# SLAMP.net
KiCad netlist of a schematic drawn in EAGLE
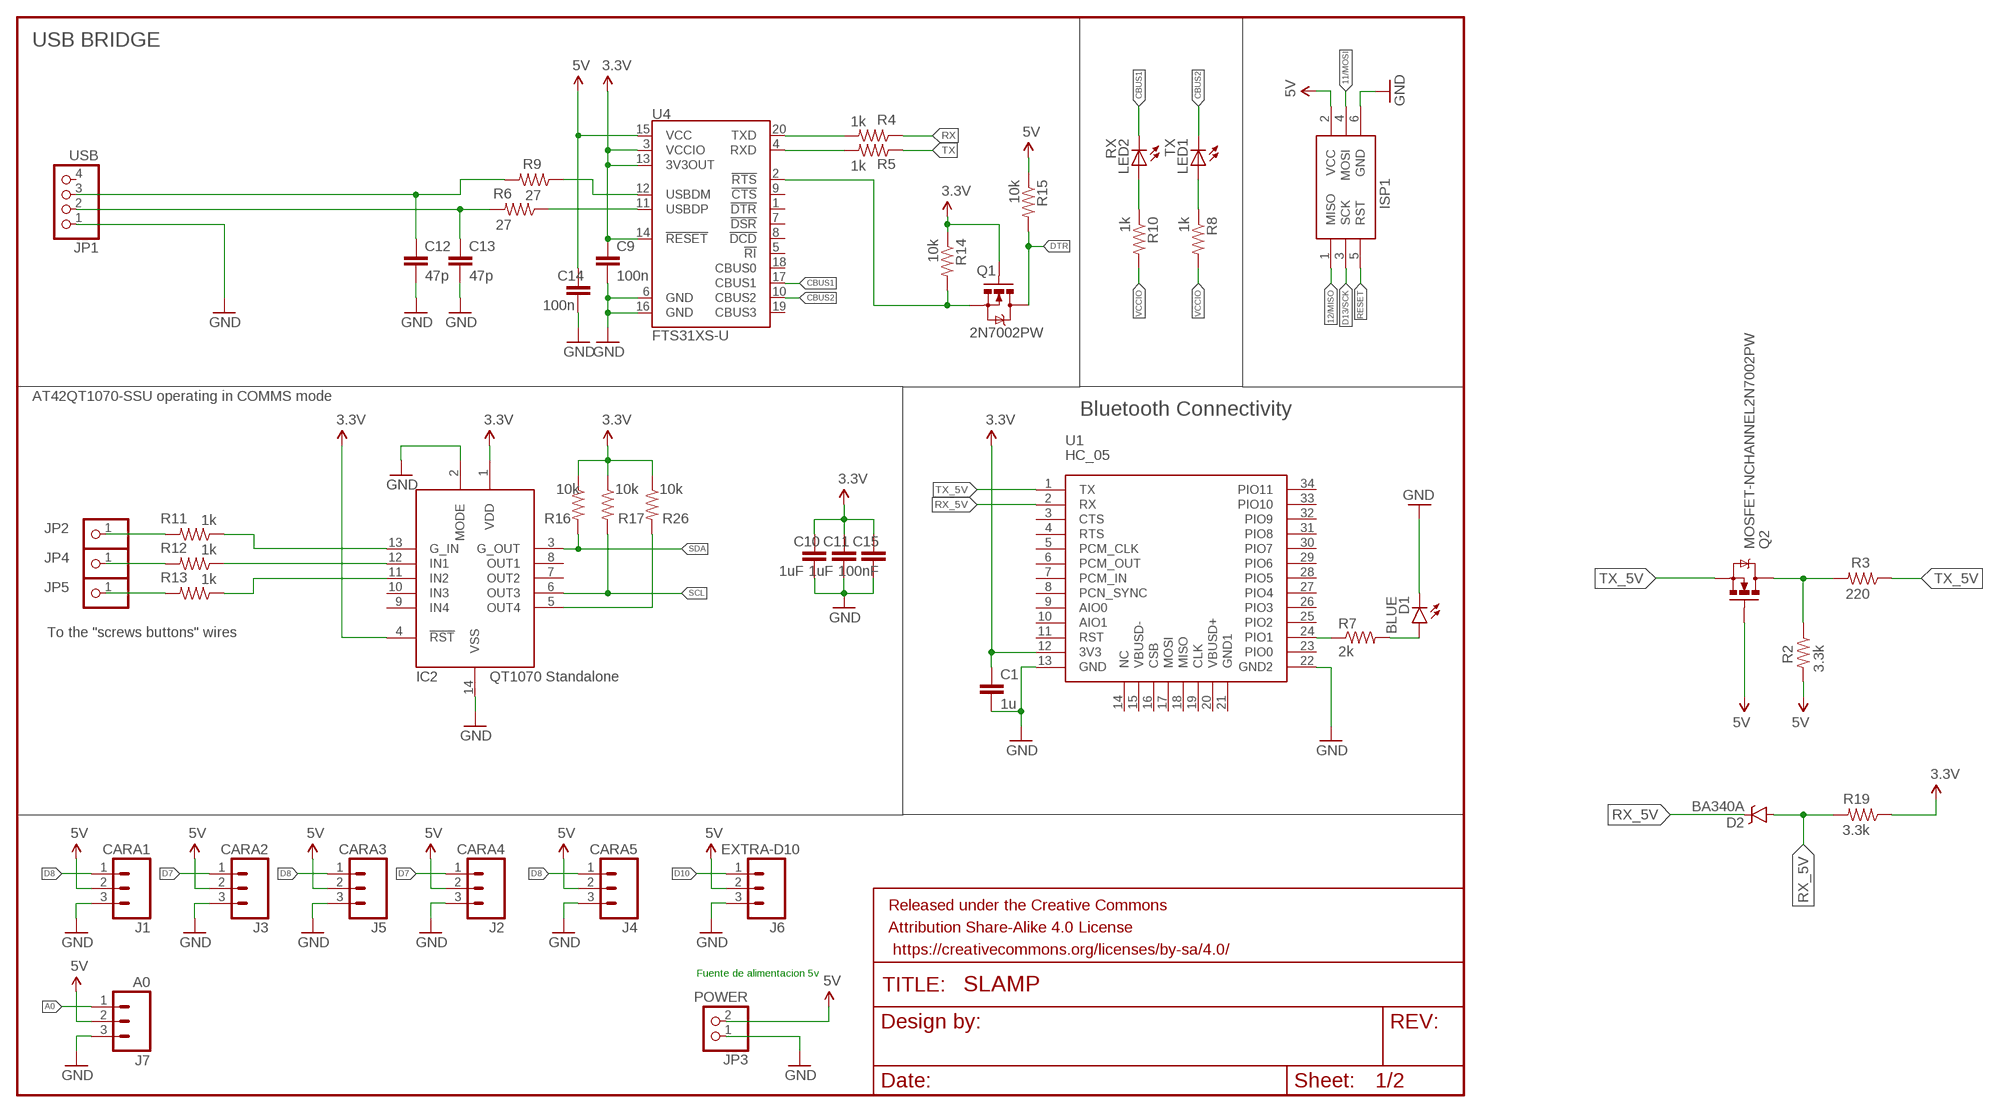
[diagram p0: schematic, sheet 1]
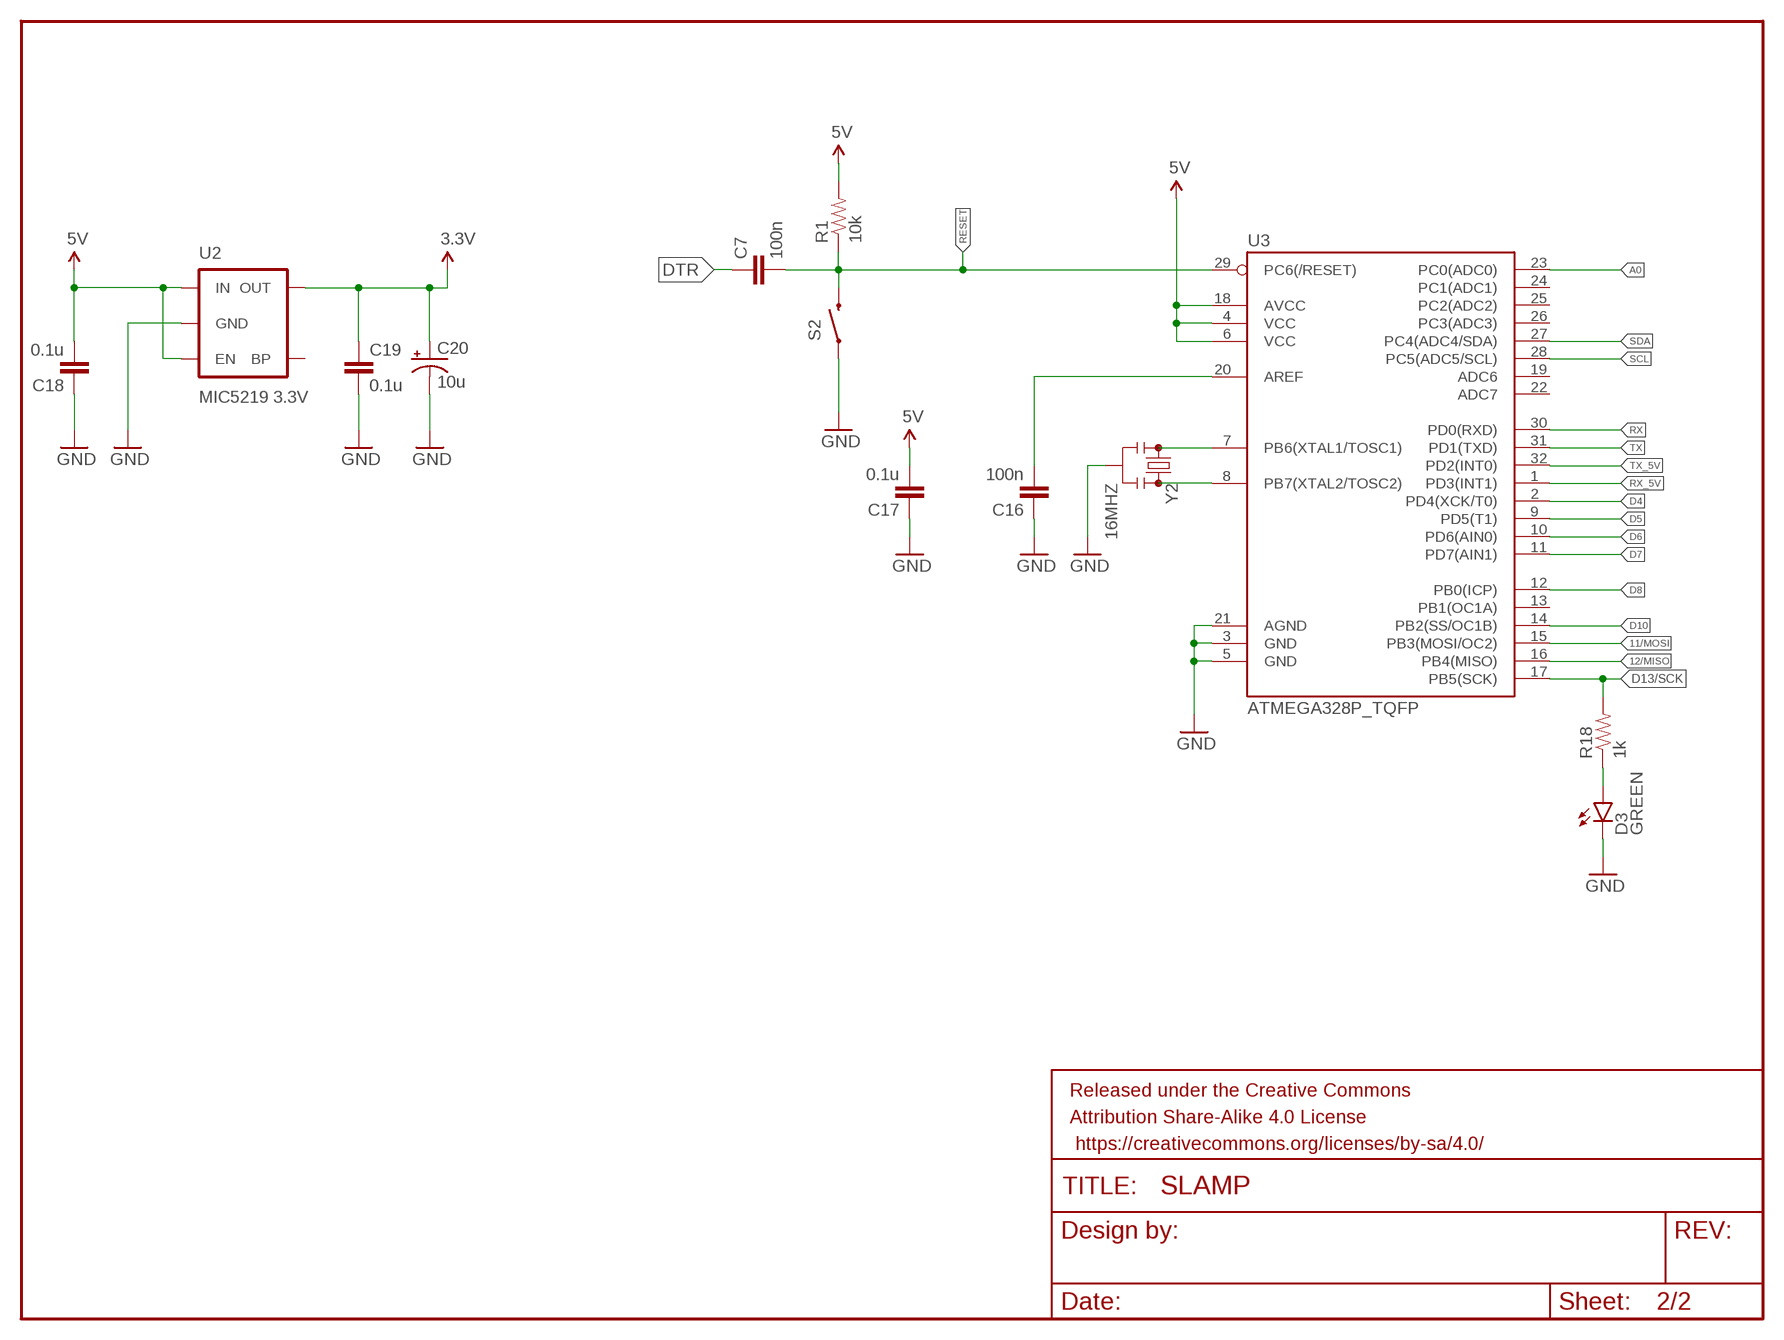
[diagram p1: schematic, sheet 2]

(export (version "E")
  (design (tool "Eeschema 10.0.6"))
  (components
    (comp (ref "C1")
      (value "1u")
      (footprint "eagle-import:0603-CAP")
      (libsource (lib "eagle-import") (part "CAP0603-CAP"))
    )
    (comp (ref "C9")
      (value "100n")
      (footprint "eagle-import:0603-CAP")
      (libsource (lib "eagle-import") (part "CAP0603-CAP"))
    )
    (comp (ref "C10")
      (value "1uF")
      (footprint "eagle-import:0603-CAP")
      (libsource (lib "eagle-import") (part "CAP0603-CAP"))
    )
    (comp (ref "C11")
      (value "1uF")
      (footprint "eagle-import:0603-CAP")
      (libsource (lib "eagle-import") (part "CAP0603-CAP"))
    )
    (comp (ref "C12")
      (value "47p")
      (footprint "eagle-import:0603-CAP")
      (libsource (lib "eagle-import") (part "CAP0603-CAP"))
    )
    (comp (ref "C13")
      (value "47p")
      (footprint "eagle-import:0603-CAP")
      (libsource (lib "eagle-import") (part "CAP0603-CAP"))
    )
    (comp (ref "C14")
      (value "100n")
      (footprint "eagle-import:0603-CAP")
      (libsource (lib "eagle-import") (part "CAP0603-CAP"))
    )
    (comp (ref "C15")
      (value "100nF")
      (footprint "eagle-import:0603-CAP")
      (libsource (lib "eagle-import") (part "CAP0603-CAP"))
    )
    (comp (ref "D1")
      (value "BLUE")
      (footprint "eagle-import:LED-0603")
      (libsource (lib "eagle-import") (part "LED-BLUE0603"))
    )
    (comp (ref "D2")
      (value "BA340A")
      (footprint "eagle-import:SMA-DIODE")
      (libsource (lib "eagle-import") (part "B340A"))
    )
    (comp (ref "FRAME1")
      (value "FRAME-LETTERNO_PACKAGE")
      (footprint "eagle-import:DUMMY")
      (fields (field (name "DESIGNER") "Nobody"))
      (libsource (lib "eagle-import") (part "FRAME-LETTERNO_PACKAGE"))
    )
    (comp (ref "IC2")
      (value "AT42QT1070-SSU")
      (footprint "eagle-import:SO14")
      (libsource (lib "eagle-import") (part "AT42QT1070-SSU"))
    )
    (comp (ref "ISP1")
      (value "AVRISP-6")
      (footprint "eagle-import:AVRISP")
      (libsource (lib "eagle-import") (part "AVRISP-6"))
    )
    (comp (ref "J1")
      (value "CARA1")
      (footprint "eagle-import:JST-3-PTH-VERT")
      (libsource (lib "eagle-import") (part "M03JST-PTH-VERT"))
    )
    (comp (ref "J2")
      (value "CARA4")
      (footprint "eagle-import:JST-3-PTH-VERT")
      (libsource (lib "eagle-import") (part "M03JST-PTH-VERT"))
    )
    (comp (ref "J3")
      (value "CARA2")
      (footprint "eagle-import:JST-3-PTH-VERT")
      (libsource (lib "eagle-import") (part "M03JST-PTH-VERT"))
    )
    (comp (ref "J4")
      (value "CARA5")
      (footprint "eagle-import:JST-3-PTH-VERT")
      (libsource (lib "eagle-import") (part "M03JST-PTH-VERT"))
    )
    (comp (ref "J5")
      (value "CARA3")
      (footprint "eagle-import:JST-3-PTH-VERT")
      (libsource (lib "eagle-import") (part "M03JST-PTH-VERT"))
    )
    (comp (ref "J6")
      (value "EXTRA-D10")
      (footprint "eagle-import:JST-3-PTH-VERT")
      (libsource (lib "eagle-import") (part "M03JST-PTH-VERT"))
    )
    (comp (ref "J7")
      (value "A0")
      (footprint "eagle-import:JST-3-PTH-VERT")
      (libsource (lib "eagle-import") (part "M03JST-PTH-VERT"))
    )
    (comp (ref "JP1")
      (value "USB")
      (footprint "eagle-import:1X04")
      (libsource (lib "eagle-import") (part "PINHD-1X4"))
    )
    (comp (ref "JP2")
      (value "PINHD-1X1")
      (footprint "eagle-import:1X01")
      (libsource (lib "eagle-import") (part "PINHD-1X1"))
    )
    (comp (ref "JP3")
      (value "POWER")
      (footprint "eagle-import:1X02")
      (libsource (lib "eagle-import") (part "PINHD-1X2"))
    )
    (comp (ref "JP4")
      (value "PINHD-1X1")
      (footprint "eagle-import:1X01")
      (libsource (lib "eagle-import") (part "PINHD-1X1"))
    )
    (comp (ref "JP5")
      (value "PINHD-1X1")
      (footprint "eagle-import:1X01")
      (libsource (lib "eagle-import") (part "PINHD-1X1"))
    )
    (comp (ref "LED1")
      (value "TX")
      (footprint "eagle-import:CHIP-LED0603")
      (libsource (lib "eagle-import") (part "LEDCHIP-LED0603"))
    )
    (comp (ref "LED2")
      (value "RX")
      (footprint "eagle-import:CHIP-LED0603")
      (libsource (lib "eagle-import") (part "LEDCHIP-LED0603"))
    )
    (comp (ref "Q1")
      (value "2N7002PW")
      (footprint "eagle-import:SOT323")
      (libsource (lib "eagle-import") (part "MOSFET-NCHANNEL2N7002PW"))
    )
    (comp (ref "Q2")
      (value "MOSFET-NCHANNEL2N7002PW")
      (footprint "eagle-import:SOT323")
      (libsource (lib "eagle-import") (part "MOSFET-NCHANNEL2N7002PW"))
    )
    (comp (ref "R2")
      (value "3.3k")
      (footprint "eagle-import:0603-RES")
      (libsource (lib "eagle-import") (part "RESISTOR0603-RES"))
    )
    (comp (ref "R3")
      (value "220")
      (footprint "eagle-import:0603-RES")
      (libsource (lib "eagle-import") (part "RESISTOR0603-RES"))
    )
    (comp (ref "R4")
      (value "1k")
      (footprint "eagle-import:0805")
      (libsource (lib "eagle-import") (part "RESISTOR0805-RES"))
    )
    (comp (ref "R5")
      (value "1k")
      (footprint "eagle-import:0805")
      (libsource (lib "eagle-import") (part "RESISTOR0805-RES"))
    )
    (comp (ref "R6")
      (value "27")
      (footprint "eagle-import:0603-RES")
      (libsource (lib "eagle-import") (part "RESISTOR0603-RES"))
    )
    (comp (ref "R7")
      (value "2k")
      (footprint "eagle-import:0805")
      (libsource (lib "eagle-import") (part "RESISTOR0805-RES"))
    )
    (comp (ref "R8")
      (value "1k")
      (footprint "eagle-import:0603-RES")
      (libsource (lib "eagle-import") (part "RESISTOR0603-RES"))
    )
    (comp (ref "R9")
      (value "27")
      (footprint "eagle-import:0603-RES")
      (libsource (lib "eagle-import") (part "RESISTOR0603-RES"))
    )
    (comp (ref "R10")
      (value "1k")
      (footprint "eagle-import:0603-RES")
      (libsource (lib "eagle-import") (part "RESISTOR0603-RES"))
    )
    (comp (ref "R11")
      (value "1k")
      (footprint "eagle-import:0603-RES")
      (libsource (lib "eagle-import") (part "RESISTOR0603-RES"))
    )
    (comp (ref "R12")
      (value "1k")
      (footprint "eagle-import:0603-RES")
      (libsource (lib "eagle-import") (part "RESISTOR0603-RES"))
    )
    (comp (ref "R13")
      (value "1k")
      (footprint "eagle-import:0603-RES")
      (libsource (lib "eagle-import") (part "RESISTOR0603-RES"))
    )
    (comp (ref "R14")
      (value "10k")
      (footprint "eagle-import:0805")
      (libsource (lib "eagle-import") (part "RESISTOR0805-RES"))
    )
    (comp (ref "R15")
      (value "10k")
      (footprint "eagle-import:0805")
      (libsource (lib "eagle-import") (part "RESISTOR0805-RES"))
    )
    (comp (ref "R16")
      (value "10k")
      (footprint "eagle-import:0603-RES")
      (libsource (lib "eagle-import") (part "RESISTOR0603-RES"))
    )
    (comp (ref "R17")
      (value "10k")
      (footprint "eagle-import:0603-RES")
      (libsource (lib "eagle-import") (part "RESISTOR0603-RES"))
    )
    (comp (ref "R19")
      (value "3.3k")
      (footprint "eagle-import:0603-RES")
      (libsource (lib "eagle-import") (part "RESISTOR0603-RES"))
    )
    (comp (ref "R26")
      (value "10k")
      (footprint "eagle-import:0603-RES")
      (libsource (lib "eagle-import") (part "RESISTOR0603-RES"))
    )
    (comp (ref "U1")
      (value "HC_05")
      (footprint "eagle-import:BLUETOOTH_SMD")
      (libsource (lib "eagle-import") (part "HC_05"))
    )
    (comp (ref "U4")
      (value "FTS31XS-U")
      (footprint "eagle-import:SSOP20_L")
      (libsource (lib "eagle-import") (part "FT231XS"))
    )
    (comp (ref "C7")
      (value "100n")
      (footprint "eagle-import:0805")
      (libsource (lib "eagle-import") (part "CAP0805"))
    )
    (comp (ref "C16")
      (value "100n")
      (footprint "eagle-import:0805")
      (libsource (lib "eagle-import") (part "CAP0805"))
    )
    (comp (ref "C17")
      (value "0.1u")
      (footprint "eagle-import:0805")
      (libsource (lib "eagle-import") (part "CAP0805"))
    )
    (comp (ref "C18")
      (value "0.1u")
      (footprint "eagle-import:0603-CAP")
      (libsource (lib "eagle-import") (part "CAP0603-CAP"))
    )
    (comp (ref "C19")
      (value "0.1u")
      (footprint "eagle-import:0603-CAP")
      (libsource (lib "eagle-import") (part "CAP0603-CAP"))
    )
    (comp (ref "C20")
      (value "10u")
      (footprint "eagle-import:SMC_P")
      (libsource (lib "eagle-import") (part "CPOL-USSMCP"))
    )
    (comp (ref "D3")
      (value "GREEN")
      (footprint "eagle-import:LED-0603")
      (libsource (lib "eagle-import") (part "LED-BLUE0603"))
    )
    (comp (ref "FRAME2")
      (value "FRAME-LETTERNO_PACKAGE")
      (footprint "eagle-import:DUMMY")
      (fields (field (name "DESIGNER") "Nobody"))
      (libsource (lib "eagle-import") (part "FRAME-LETTERNO_PACKAGE"))
    )
    (comp (ref "R1")
      (value "10k")
      (footprint "eagle-import:0805")
      (libsource (lib "eagle-import") (part "RESISTOR0805-RES"))
    )
    (comp (ref "R18")
      (value "1k")
      (footprint "eagle-import:0805")
      (libsource (lib "eagle-import") (part "RESISTOR0805-RES"))
    )
    (comp (ref "S2")
      (value "SWITCH-MOMENTARY-2PTH")
      (footprint "eagle-import:TACTILE-PTH")
      (libsource (lib "eagle-import") (part "SWITCH-MOMENTARY-2PTH"))
    )
    (comp (ref "U2")
      (value "MIC5219 3.3V")
      (footprint "eagle-import:SOT23-5")
      (libsource (lib "eagle-import") (part "V_REG_MIC52193.3V"))
    )
    (comp (ref "U3")
      (value "ATMEGA328P_TQFP")
      (footprint "eagle-import:TQFP32-08")
      (libsource (lib "eagle-import") (part "ATMEGA328P_TQFP"))
    )
    (comp (ref "Y2")
      (value "16MHZ")
      (footprint "eagle-import:RESONATOR-SMD")
      (libsource (lib "eagle-import") (part "RESONATOR16MHZ"))
    )
  )
  (nets
    (net (code "1") (name "3.3V") (class "Default")
      (node (ref "C1") (pin "1") (pinfunction "1_1") (pintype "passive"))
      (node (ref "C10") (pin "1") (pinfunction "1_1") (pintype "passive"))
      (node (ref "C11") (pin "1") (pinfunction "1_1") (pintype "passive"))
      (node (ref "C15") (pin "1") (pinfunction "1_1") (pintype "passive"))
      (node (ref "C19") (pin "1") (pinfunction "1_1") (pintype "passive"))
      (node (ref "C20") (pin "+") (pinfunction "+_+") (pintype "passive"))
      (node (ref "C9") (pin "1") (pinfunction "1_1") (pintype "passive"))
      (node (ref "IC2") (pin "1") (pinfunction "VDD_1") (pintype "power_in"))
      (node (ref "IC2") (pin "4") (pinfunction "~{RST}_4") (pintype "input"))
      (node (ref "Q1") (pin "1") (pinfunction "G_1") (pintype "passive"))
      (node (ref "R14") (pin "1") (pinfunction "1_1") (pintype "passive"))
      (node (ref "R16") (pin "1") (pinfunction "1_1") (pintype "passive"))
      (node (ref "R17") (pin "1") (pinfunction "1_1") (pintype "passive"))
      (node (ref "R19") (pin "1") (pinfunction "1_1") (pintype "passive"))
      (node (ref "R26") (pin "1") (pinfunction "1_1") (pintype "passive"))
      (node (ref "U1") (pin "12") (pinfunction "3V3_12") (pintype "bidirectional"))
      (node (ref "U2") (pin "5") (pinfunction "OUT_5") (pintype "passive"))
      (node (ref "U4") (pin "13") (pinfunction "3V3OUT_13") (pintype "bidirectional"))
      (node (ref "U4") (pin "14") (pinfunction "~{RESET}_14") (pintype "bidirectional"))
      (node (ref "U4") (pin "3") (pinfunction "VCCIO_3") (pintype "bidirectional"))
    )
    (net (code "2") (name "5V") (class "Default")
      (node (ref "C14") (pin "1") (pinfunction "1_1") (pintype "passive"))
      (node (ref "C17") (pin "2") (pinfunction "2_2") (pintype "passive"))
      (node (ref "C18") (pin "2") (pinfunction "2_2") (pintype "passive"))
      (node (ref "ISP1") (pin "2") (pinfunction "VCC_2") (pintype "power_in"))
      (node (ref "J1") (pin "2") (pinfunction "2_2") (pintype "passive"))
      (node (ref "J2") (pin "2") (pinfunction "2_2") (pintype "passive"))
      (node (ref "J3") (pin "2") (pinfunction "2_2") (pintype "passive"))
      (node (ref "J4") (pin "2") (pinfunction "2_2") (pintype "passive"))
      (node (ref "J5") (pin "2") (pinfunction "2_2") (pintype "passive"))
      (node (ref "J6") (pin "2") (pinfunction "2_2") (pintype "passive"))
      (node (ref "J7") (pin "2") (pinfunction "2_2") (pintype "passive"))
      (node (ref "JP3") (pin "2") (pinfunction "2_2") (pintype "passive"))
      (node (ref "Q2") (pin "1") (pinfunction "G_1") (pintype "passive"))
      (node (ref "R1") (pin "2") (pinfunction "2_2") (pintype "passive"))
      (node (ref "R15") (pin "1") (pinfunction "1_1") (pintype "passive"))
      (node (ref "R2") (pin "2") (pinfunction "2_2") (pintype "passive"))
      (node (ref "U2") (pin "1") (pinfunction "IN_1") (pintype "input"))
      (node (ref "U2") (pin "3") (pinfunction "EN_3") (pintype "input"))
      (node (ref "U3") (pin "18") (pinfunction "AVCC_18") (pintype "bidirectional"))
      (node (ref "U3") (pin "4") (pinfunction "VCC_4") (pintype "bidirectional"))
      (node (ref "U3") (pin "6") (pinfunction "VCC_6") (pintype "bidirectional"))
      (node (ref "U4") (pin "15") (pinfunction "VCC_15") (pintype "bidirectional"))
    )
    (net (code "3") (name "11{slash}MOSI") (class "Default")
      (node (ref "ISP1") (pin "4") (pinfunction "MOSI_4") (pintype "output"))
      (node (ref "U3") (pin "15") (pinfunction "PB3(MOSI/OC2)_15") (pintype "bidirectional"))
    )
    (net (code "4") (name "12{slash}MISO") (class "Default")
      (node (ref "ISP1") (pin "1") (pinfunction "MISO_1") (pintype "input"))
      (node (ref "U3") (pin "16") (pinfunction "PB4(MISO)_16") (pintype "bidirectional"))
    )
    (net (code "5") (name "A0") (class "Default")
      (node (ref "J7") (pin "1") (pinfunction "1_1") (pintype "passive"))
      (node (ref "U3") (pin "23") (pinfunction "PC0(ADC0)_23") (pintype "bidirectional"))
    )
    (net (code "6") (name "CBUS1") (class "Default")
      (node (ref "LED2") (pin "C") (pinfunction "C_C") (pintype "passive"))
      (node (ref "U4") (pin "17") (pinfunction "CBUS1_17") (pintype "bidirectional"))
    )
    (net (code "7") (name "CBUS2") (class "Default")
      (node (ref "LED1") (pin "C") (pinfunction "C_C") (pintype "passive"))
      (node (ref "U4") (pin "10") (pinfunction "CBUS2_10") (pintype "bidirectional"))
    )
    (net (code "8") (name "D4") (class "Default")
      (node (ref "U3") (pin "2") (pinfunction "PD4(XCK/T0)_2") (pintype "bidirectional"))
    )
    (net (code "9") (name "D5") (class "Default")
      (node (ref "U3") (pin "9") (pinfunction "PD5(T1)_9") (pintype "bidirectional"))
    )
    (net (code "10") (name "D6") (class "Default")
      (node (ref "U3") (pin "10") (pinfunction "PD6(AIN0)_10") (pintype "bidirectional"))
    )
    (net (code "11") (name "D7") (class "Default")
      (node (ref "J2") (pin "1") (pinfunction "1_1") (pintype "passive"))
      (node (ref "J3") (pin "1") (pinfunction "1_1") (pintype "passive"))
      (node (ref "U3") (pin "11") (pinfunction "PD7(AIN1)_11") (pintype "bidirectional"))
    )
    (net (code "12") (name "D8") (class "Default")
      (node (ref "J1") (pin "1") (pinfunction "1_1") (pintype "passive"))
      (node (ref "J4") (pin "1") (pinfunction "1_1") (pintype "passive"))
      (node (ref "J5") (pin "1") (pinfunction "1_1") (pintype "passive"))
      (node (ref "U3") (pin "12") (pinfunction "PB0(ICP)_12") (pintype "bidirectional"))
    )
    (net (code "13") (name "D10") (class "Default")
      (node (ref "J6") (pin "1") (pinfunction "1_1") (pintype "passive"))
      (node (ref "U3") (pin "14") (pinfunction "PB2(SS/OC1B)_14") (pintype "bidirectional"))
    )
    (net (code "14") (name "D13{slash}SCK") (class "Default")
      (node (ref "ISP1") (pin "3") (pinfunction "SCK_3") (pintype "output"))
      (node (ref "R18") (pin "2") (pinfunction "2_2") (pintype "passive"))
      (node (ref "U3") (pin "17") (pinfunction "PB5(SCK)_17") (pintype "bidirectional"))
    )
    (net (code "15") (name "DTR") (class "Default")
      (node (ref "C7") (pin "1") (pinfunction "1_1") (pintype "passive"))
      (node (ref "Q1") (pin "3") (pinfunction "D_3") (pintype "passive"))
      (node (ref "R15") (pin "2") (pinfunction "2_2") (pintype "passive"))
    )
    (net (code "16") (name "GND") (class "Default")
      (node (ref "C1") (pin "2") (pinfunction "2_2") (pintype "passive"))
      (node (ref "C10") (pin "2") (pinfunction "2_2") (pintype "passive"))
      (node (ref "C11") (pin "2") (pinfunction "2_2") (pintype "passive"))
      (node (ref "C12") (pin "2") (pinfunction "2_2") (pintype "passive"))
      (node (ref "C13") (pin "2") (pinfunction "2_2") (pintype "passive"))
      (node (ref "C14") (pin "2") (pinfunction "2_2") (pintype "passive"))
      (node (ref "C15") (pin "2") (pinfunction "2_2") (pintype "passive"))
      (node (ref "C16") (pin "1") (pinfunction "1_1") (pintype "passive"))
      (node (ref "C17") (pin "1") (pinfunction "1_1") (pintype "passive"))
      (node (ref "C18") (pin "1") (pinfunction "1_1") (pintype "passive"))
      (node (ref "C19") (pin "2") (pinfunction "2_2") (pintype "passive"))
      (node (ref "C20") (pin "-") (pinfunction "-_-") (pintype "passive"))
      (node (ref "C9") (pin "2") (pinfunction "2_2") (pintype "passive"))
      (node (ref "D1") (pin "C") (pinfunction "C_C") (pintype "passive"))
      (node (ref "D3") (pin "C") (pinfunction "C_C") (pintype "passive"))
      (node (ref "IC2") (pin "14") (pinfunction "VSS_14") (pintype "power_in"))
      (node (ref "IC2") (pin "2") (pinfunction "MODE_2") (pintype "input"))
      (node (ref "ISP1") (pin "6") (pinfunction "GND_6") (pintype "power_in"))
      (node (ref "J1") (pin "3") (pinfunction "3_3") (pintype "passive"))
      (node (ref "J2") (pin "3") (pinfunction "3_3") (pintype "passive"))
      (node (ref "J3") (pin "3") (pinfunction "3_3") (pintype "passive"))
      (node (ref "J4") (pin "3") (pinfunction "3_3") (pintype "passive"))
      (node (ref "J5") (pin "3") (pinfunction "3_3") (pintype "passive"))
      (node (ref "J6") (pin "3") (pinfunction "3_3") (pintype "passive"))
      (node (ref "J7") (pin "3") (pinfunction "3_3") (pintype "passive"))
      (node (ref "JP1") (pin "1") (pinfunction "1_1") (pintype "passive"))
      (node (ref "JP3") (pin "1") (pinfunction "1_1") (pintype "passive"))
      (node (ref "S2") (pin "1") (pinfunction "1_1") (pintype "passive"))
      (node (ref "U1") (pin "13") (pinfunction "GND_13") (pintype "bidirectional"))
      (node (ref "U1") (pin "22") (pinfunction "GND2_22") (pintype "bidirectional"))
      (node (ref "U2") (pin "2") (pinfunction "GND_2") (pintype "input"))
      (node (ref "U3") (pin "21") (pinfunction "AGND_21") (pintype "bidirectional"))
      (node (ref "U3") (pin "3") (pinfunction "GND_3") (pintype "bidirectional"))
      (node (ref "U3") (pin "5") (pinfunction "GND_5") (pintype "bidirectional"))
      (node (ref "U4") (pin "16") (pinfunction "GND_16") (pintype "bidirectional"))
      (node (ref "U4") (pin "6") (pinfunction "GND_6") (pintype "bidirectional"))
      (node (ref "Y2") (pin "2") (pinfunction "2_2") (pintype "passive"))
    )
    (net (code "17") (name "Net-(C12-Pad1)") (class "Default")
      (node (ref "C12") (pin "1") (pinfunction "1_1") (pintype "passive"))
      (node (ref "JP1") (pin "3") (pinfunction "3_3") (pintype "passive"))
      (node (ref "R9") (pin "2") (pinfunction "2_2") (pintype "passive"))
    )
    (net (code "18") (name "Net-(C13-Pad1)") (class "Default")
      (node (ref "C13") (pin "1") (pinfunction "1_1") (pintype "passive"))
      (node (ref "JP1") (pin "2") (pinfunction "2_2") (pintype "passive"))
      (node (ref "R6") (pin "2") (pinfunction "2_2") (pintype "passive"))
    )
    (net (code "19") (name "Net-(D1-PadA)") (class "Default")
      (node (ref "D1") (pin "A") (pinfunction "A_A") (pintype "passive"))
      (node (ref "R7") (pin "2") (pinfunction "2_2") (pintype "passive"))
    )
    (net (code "20") (name "Net-(D3-PadA)") (class "Default")
      (node (ref "D3") (pin "A") (pinfunction "A_A") (pintype "passive"))
      (node (ref "R18") (pin "1") (pinfunction "1_1") (pintype "passive"))
    )
    (net (code "21") (name "Net-(IC2-G_IN)") (class "Default")
      (node (ref "IC2") (pin "13") (pinfunction "G_IN_13") (pintype "input"))
      (node (ref "R11") (pin "1") (pinfunction "1_1") (pintype "passive"))
    )
    (net (code "22") (name "Net-(IC2-IN1)") (class "Default")
      (node (ref "IC2") (pin "12") (pinfunction "IN1_12") (pintype "input"))
      (node (ref "R12") (pin "1") (pinfunction "1_1") (pintype "passive"))
    )
    (net (code "23") (name "Net-(IC2-IN2)") (class "Default")
      (node (ref "IC2") (pin "11") (pinfunction "IN2_11") (pintype "input"))
      (node (ref "R13") (pin "1") (pinfunction "1_1") (pintype "passive"))
    )
    (net (code "24") (name "Net-(IC2-OUT4)") (class "Default")
      (node (ref "IC2") (pin "5") (pinfunction "OUT4_5") (pintype "open_collector"))
      (node (ref "R26") (pin "2") (pinfunction "2_2") (pintype "passive"))
    )
    (net (code "25") (name "Net-(JP2-Pad1)") (class "Default")
      (node (ref "JP2") (pin "1") (pinfunction "1_1") (pintype "passive"))
      (node (ref "R11") (pin "2") (pinfunction "2_2") (pintype "passive"))
    )
    (net (code "26") (name "Net-(JP4-Pad1)") (class "Default")
      (node (ref "JP4") (pin "1") (pinfunction "1_1") (pintype "passive"))
      (node (ref "R12") (pin "2") (pinfunction "2_2") (pintype "passive"))
    )
    (net (code "27") (name "Net-(JP5-Pad1)") (class "Default")
      (node (ref "JP5") (pin "1") (pinfunction "1_1") (pintype "passive"))
      (node (ref "R13") (pin "2") (pinfunction "2_2") (pintype "passive"))
    )
    (net (code "28") (name "Net-(LED1-PadA)") (class "Default")
      (node (ref "LED1") (pin "A") (pinfunction "A_A") (pintype "passive"))
      (node (ref "R8") (pin "1") (pinfunction "1_1") (pintype "passive"))
    )
    (net (code "29") (name "Net-(LED2-PadA)") (class "Default")
      (node (ref "LED2") (pin "A") (pinfunction "A_A") (pintype "passive"))
      (node (ref "R10") (pin "1") (pinfunction "1_1") (pintype "passive"))
    )
    (net (code "30") (name "Net-(Q1-S)") (class "Default")
      (node (ref "Q1") (pin "2") (pinfunction "S_2") (pintype "passive"))
      (node (ref "R14") (pin "2") (pinfunction "2_2") (pintype "passive"))
      (node (ref "U4") (pin "2") (pinfunction "~{RTS}_2") (pintype "bidirectional"))
    )
    (net (code "31") (name "Net-(Q2-D)") (class "Default")
      (node (ref "Q2") (pin "3") (pinfunction "D_3") (pintype "passive"))
      (node (ref "R2") (pin "1") (pinfunction "1_1") (pintype "passive"))
      (node (ref "R3") (pin "2") (pinfunction "2_2") (pintype "passive"))
    )
    (net (code "32") (name "Net-(U1-PIO1)") (class "Default")
      (node (ref "R7") (pin "1") (pinfunction "1_1") (pintype "passive"))
      (node (ref "U1") (pin "24") (pinfunction "PIO1_24") (pintype "bidirectional"))
    )
    (net (code "33") (name "Net-(U3-AREF)") (class "Default")
      (node (ref "C16") (pin "2") (pinfunction "2_2") (pintype "passive"))
      (node (ref "U3") (pin "20") (pinfunction "AREF_20") (pintype "bidirectional"))
    )
    (net (code "34") (name "Net-(U3-PB6(XTAL1{slash}TOSC1))") (class "Default")
      (node (ref "U3") (pin "7") (pinfunction "PB6(XTAL1/TOSC1)_7") (pintype "bidirectional"))
      (node (ref "Y2") (pin "1") (pinfunction "1_1") (pintype "passive"))
    )
    (net (code "35") (name "Net-(U3-PB7(XTAL2{slash}TOSC2))") (class "Default")
      (node (ref "U3") (pin "8") (pinfunction "PB7(XTAL2/TOSC2)_8") (pintype "bidirectional"))
      (node (ref "Y2") (pin "3") (pinfunction "3_3") (pintype "passive"))
    )
    (net (code "36") (name "Net-(U4-USBDM)") (class "Default")
      (node (ref "R9") (pin "1") (pinfunction "1_1") (pintype "passive"))
      (node (ref "U4") (pin "12") (pinfunction "USBDM_12") (pintype "bidirectional"))
    )
    (net (code "37") (name "Net-(U4-USBDP)") (class "Default")
      (node (ref "R6") (pin "1") (pinfunction "1_1") (pintype "passive"))
      (node (ref "U4") (pin "11") (pinfunction "USBDP_11") (pintype "bidirectional"))
    )
    (net (code "38") (name "RESET") (class "Default")
      (node (ref "C7") (pin "2") (pinfunction "2_2") (pintype "passive"))
      (node (ref "ISP1") (pin "5") (pinfunction "RST_5") (pintype "output"))
      (node (ref "R1") (pin "1") (pinfunction "1_1") (pintype "passive"))
      (node (ref "S2") (pin "3") (pinfunction "2_3") (pintype "passive"))
      (node (ref "U3") (pin "29") (pinfunction "PC6(/RESET)_29") (pintype "bidirectional"))
    )
    (net (code "39") (name "RX") (class "Default")
      (node (ref "R4") (pin "1") (pinfunction "1_1") (pintype "passive"))
      (node (ref "R5") (pin "2") (pinfunction "2_2") (pintype "passive"))
      (node (ref "U3") (pin "30") (pinfunction "PD0(RXD)_30") (pintype "bidirectional"))
      (node (ref "U4") (pin "4") (pinfunction "RXD_4") (pintype "bidirectional"))
    )
    (net (code "40") (name "RX_5V") (class "Default")
      (node (ref "D2") (pin "A") (pinfunction "A_A") (pintype "passive"))
      (node (ref "D2") (pin "C") (pinfunction "C_C") (pintype "passive"))
      (node (ref "R19") (pin "2") (pinfunction "2_2") (pintype "passive"))
      (node (ref "U1") (pin "2") (pinfunction "RX_2") (pintype "bidirectional"))
      (node (ref "U3") (pin "1") (pinfunction "PD3(INT1)_1") (pintype "bidirectional"))
    )
    (net (code "41") (name "SCL") (class "Default")
      (node (ref "IC2") (pin "6") (pinfunction "OUT3_6") (pintype "open_collector"))
      (node (ref "R17") (pin "2") (pinfunction "2_2") (pintype "passive"))
      (node (ref "U3") (pin "28") (pinfunction "PC5(ADC5/SCL)_28") (pintype "bidirectional"))
    )
    (net (code "42") (name "SDA") (class "Default")
      (node (ref "IC2") (pin "3") (pinfunction "G_OUT_3") (pintype "open_collector"))
      (node (ref "R16") (pin "2") (pinfunction "2_2") (pintype "passive"))
      (node (ref "U3") (pin "27") (pinfunction "PC4(ADC4/SDA)_27") (pintype "bidirectional"))
    )
    (net (code "43") (name "TX") (class "Default")
      (node (ref "R4") (pin "2") (pinfunction "2_2") (pintype "passive"))
      (node (ref "R5") (pin "1") (pinfunction "1_1") (pintype "passive"))
      (node (ref "U3") (pin "31") (pinfunction "PD1(TXD)_31") (pintype "bidirectional"))
      (node (ref "U4") (pin "20") (pinfunction "TXD_20") (pintype "bidirectional"))
    )
    (net (code "44") (name "TX_5V") (class "Default")
      (node (ref "Q2") (pin "2") (pinfunction "S_2") (pintype "passive"))
      (node (ref "R3") (pin "1") (pinfunction "1_1") (pintype "passive"))
      (node (ref "U1") (pin "1") (pinfunction "TX_1") (pintype "bidirectional"))
      (node (ref "U3") (pin "32") (pinfunction "PD2(INT0)_32") (pintype "bidirectional"))
    )
    (net (code "45") (name "VCCIO") (class "Default")
      (node (ref "R10") (pin "2") (pinfunction "2_2") (pintype "passive"))
      (node (ref "R8") (pin "2") (pinfunction "2_2") (pintype "passive"))
    )
    (net (code "46") (name "unconnected-(IC2-IN3-Pad10)") (class "Default")
      (node (ref "IC2") (pin "10") (pinfunction "IN3_10") (pintype "input"))
    )
    (net (code "47") (name "unconnected-(IC2-IN4-Pad9)") (class "Default")
      (node (ref "IC2") (pin "9") (pinfunction "IN4_9") (pintype "input"))
    )
    (net (code "48") (name "unconnected-(IC2-OUT1-Pad8)") (class "Default")
      (node (ref "IC2") (pin "8") (pinfunction "OUT1_8") (pintype "open_collector"))
    )
    (net (code "49") (name "unconnected-(IC2-OUT2-Pad7)") (class "Default")
      (node (ref "IC2") (pin "7") (pinfunction "OUT2_7") (pintype "open_collector"))
    )
    (net (code "50") (name "unconnected-(JP1-Pad4)") (class "Default")
      (node (ref "JP1") (pin "4") (pinfunction "4_4") (pintype "passive"))
    )
    (net (code "51") (name "unconnected-(U1-AIO0-Pad9)") (class "Default")
      (node (ref "U1") (pin "9") (pinfunction "AIO0_9") (pintype "bidirectional"))
    )
    (net (code "52") (name "unconnected-(U1-AIO1-Pad10)") (class "Default")
      (node (ref "U1") (pin "10") (pinfunction "AIO1_10") (pintype "bidirectional"))
    )
    (net (code "53") (name "unconnected-(U1-CLK-Pad19)") (class "Default")
      (node (ref "U1") (pin "19") (pinfunction "CLK_19") (pintype "bidirectional"))
    )
    (net (code "54") (name "unconnected-(U1-CSB-Pad16)") (class "Default")
      (node (ref "U1") (pin "16") (pinfunction "CSB_16") (pintype "bidirectional"))
    )
    (net (code "55") (name "unconnected-(U1-CTS-Pad3)") (class "Default")
      (node (ref "U1") (pin "3") (pinfunction "CTS_3") (pintype "bidirectional"))
    )
    (net (code "56") (name "unconnected-(U1-GND1-Pad21)") (class "Default")
      (node (ref "U1") (pin "21") (pinfunction "GND1_21") (pintype "bidirectional"))
    )
    (net (code "57") (name "unconnected-(U1-MISO-Pad18)") (class "Default")
      (node (ref "U1") (pin "18") (pinfunction "MISO_18") (pintype "bidirectional"))
    )
    (net (code "58") (name "unconnected-(U1-MOSI-Pad17)") (class "Default")
      (node (ref "U1") (pin "17") (pinfunction "MOSI_17") (pintype "bidirectional"))
    )
    (net (code "59") (name "unconnected-(U1-NC-Pad14)") (class "Default")
      (node (ref "U1") (pin "14") (pinfunction "NC_14") (pintype "bidirectional"))
    )
    (net (code "60") (name "unconnected-(U1-PCM_CLK-Pad5)") (class "Default")
      (node (ref "U1") (pin "5") (pinfunction "PCM_CLK_5") (pintype "bidirectional"))
    )
    (net (code "61") (name "unconnected-(U1-PCM_IN-Pad7)") (class "Default")
      (node (ref "U1") (pin "7") (pinfunction "PCM_IN_7") (pintype "bidirectional"))
    )
    (net (code "62") (name "unconnected-(U1-PCM_OUT-Pad6)") (class "Default")
      (node (ref "U1") (pin "6") (pinfunction "PCM_OUT_6") (pintype "bidirectional"))
    )
    (net (code "63") (name "unconnected-(U1-PCN_SYNC-Pad8)") (class "Default")
      (node (ref "U1") (pin "8") (pinfunction "PCN_SYNC_8") (pintype "bidirectional"))
    )
    (net (code "64") (name "unconnected-(U1-PIO0-Pad23)") (class "Default")
      (node (ref "U1") (pin "23") (pinfunction "PIO0_23") (pintype "bidirectional"))
    )
    (net (code "65") (name "unconnected-(U1-PIO2-Pad25)") (class "Default")
      (node (ref "U1") (pin "25") (pinfunction "PIO2_25") (pintype "bidirectional"))
    )
    (net (code "66") (name "unconnected-(U1-PIO3-Pad26)") (class "Default")
      (node (ref "U1") (pin "26") (pinfunction "PIO3_26") (pintype "bidirectional"))
    )
    (net (code "67") (name "unconnected-(U1-PIO4-Pad27)") (class "Default")
      (node (ref "U1") (pin "27") (pinfunction "PIO4_27") (pintype "bidirectional"))
    )
    (net (code "68") (name "unconnected-(U1-PIO5-Pad28)") (class "Default")
      (node (ref "U1") (pin "28") (pinfunction "PIO5_28") (pintype "bidirectional"))
    )
    (net (code "69") (name "unconnected-(U1-PIO6-Pad29)") (class "Default")
      (node (ref "U1") (pin "29") (pinfunction "PIO6_29") (pintype "bidirectional"))
    )
    (net (code "70") (name "unconnected-(U1-PIO7-Pad30)") (class "Default")
      (node (ref "U1") (pin "30") (pinfunction "PIO7_30") (pintype "bidirectional"))
    )
    (net (code "71") (name "unconnected-(U1-PIO8-Pad31)") (class "Default")
      (node (ref "U1") (pin "31") (pinfunction "PIO8_31") (pintype "bidirectional"))
    )
    (net (code "72") (name "unconnected-(U1-PIO9-Pad32)") (class "Default")
      (node (ref "U1") (pin "32") (pinfunction "PIO9_32") (pintype "bidirectional"))
    )
    (net (code "73") (name "unconnected-(U1-PIO10-Pad33)") (class "Default")
      (node (ref "U1") (pin "33") (pinfunction "PIO10_33") (pintype "bidirectional"))
    )
    (net (code "74") (name "unconnected-(U1-PIO11-Pad34)") (class "Default")
      (node (ref "U1") (pin "34") (pinfunction "PIO11_34") (pintype "bidirectional"))
    )
    (net (code "75") (name "unconnected-(U1-RST-Pad11)") (class "Default")
      (node (ref "U1") (pin "11") (pinfunction "RST_11") (pintype "bidirectional"))
    )
    (net (code "76") (name "unconnected-(U1-RTS-Pad4)") (class "Default")
      (node (ref "U1") (pin "4") (pinfunction "RTS_4") (pintype "bidirectional"))
    )
    (net (code "77") (name "unconnected-(U1-VBUSD+-Pad20)") (class "Default")
      (node (ref "U1") (pin "20") (pinfunction "VBUSD+_20") (pintype "bidirectional"))
    )
    (net (code "78") (name "unconnected-(U1-VBUSD--Pad15)") (class "Default")
      (node (ref "U1") (pin "15") (pinfunction "VBUSD-_15") (pintype "bidirectional"))
    )
    (net (code "79") (name "unconnected-(U2-BP-Pad4)") (class "Default")
      (node (ref "U2") (pin "4") (pinfunction "BP_4") (pintype "input"))
    )
    (net (code "80") (name "unconnected-(U3-ADC6-Pad19)") (class "Default")
      (node (ref "U3") (pin "19") (pinfunction "ADC6_19") (pintype "bidirectional"))
    )
    (net (code "81") (name "unconnected-(U3-ADC7-Pad22)") (class "Default")
      (node (ref "U3") (pin "22") (pinfunction "ADC7_22") (pintype "bidirectional"))
    )
    (net (code "82") (name "unconnected-(U3-PB1(OC1A)-Pad13)") (class "Default")
      (node (ref "U3") (pin "13") (pinfunction "PB1(OC1A)_13") (pintype "bidirectional"))
    )
    (net (code "83") (name "unconnected-(U3-PC1(ADC1)-Pad24)") (class "Default")
      (node (ref "U3") (pin "24") (pinfunction "PC1(ADC1)_24") (pintype "bidirectional"))
    )
    (net (code "84") (name "unconnected-(U3-PC2(ADC2)-Pad25)") (class "Default")
      (node (ref "U3") (pin "25") (pinfunction "PC2(ADC2)_25") (pintype "bidirectional"))
    )
    (net (code "85") (name "unconnected-(U3-PC3(ADC3)-Pad26)") (class "Default")
      (node (ref "U3") (pin "26") (pinfunction "PC3(ADC3)_26") (pintype "bidirectional"))
    )
    (net (code "86") (name "unconnected-(U4-CBUS0-Pad18)") (class "Default")
      (node (ref "U4") (pin "18") (pinfunction "CBUS0_18") (pintype "bidirectional"))
    )
    (net (code "87") (name "unconnected-(U4-CBUS3-Pad19)") (class "Default")
      (node (ref "U4") (pin "19") (pinfunction "CBUS3_19") (pintype "bidirectional"))
    )
    (net (code "88") (name "unconnected-(U4-~{CTS}-Pad9)") (class "Default")
      (node (ref "U4") (pin "9") (pinfunction "~{CTS}_9") (pintype "bidirectional"))
    )
    (net (code "89") (name "unconnected-(U4-~{DCD}-Pad8)") (class "Default")
      (node (ref "U4") (pin "8") (pinfunction "~{DCD}_8") (pintype "bidirectional"))
    )
    (net (code "90") (name "unconnected-(U4-~{DSR}-Pad7)") (class "Default")
      (node (ref "U4") (pin "7") (pinfunction "~{DSR}_7") (pintype "bidirectional"))
    )
    (net (code "91") (name "unconnected-(U4-~{DTR}-Pad1)") (class "Default")
      (node (ref "U4") (pin "1") (pinfunction "~{DTR}_1") (pintype "bidirectional"))
    )
    (net (code "92") (name "unconnected-(U4-~{RI}-Pad5)") (class "Default")
      (node (ref "U4") (pin "5") (pinfunction "~{RI}_5") (pintype "bidirectional"))
    )
  )
)
